# main_controller_board.net
KiCad netlist of a schematic drawn in EAGLE
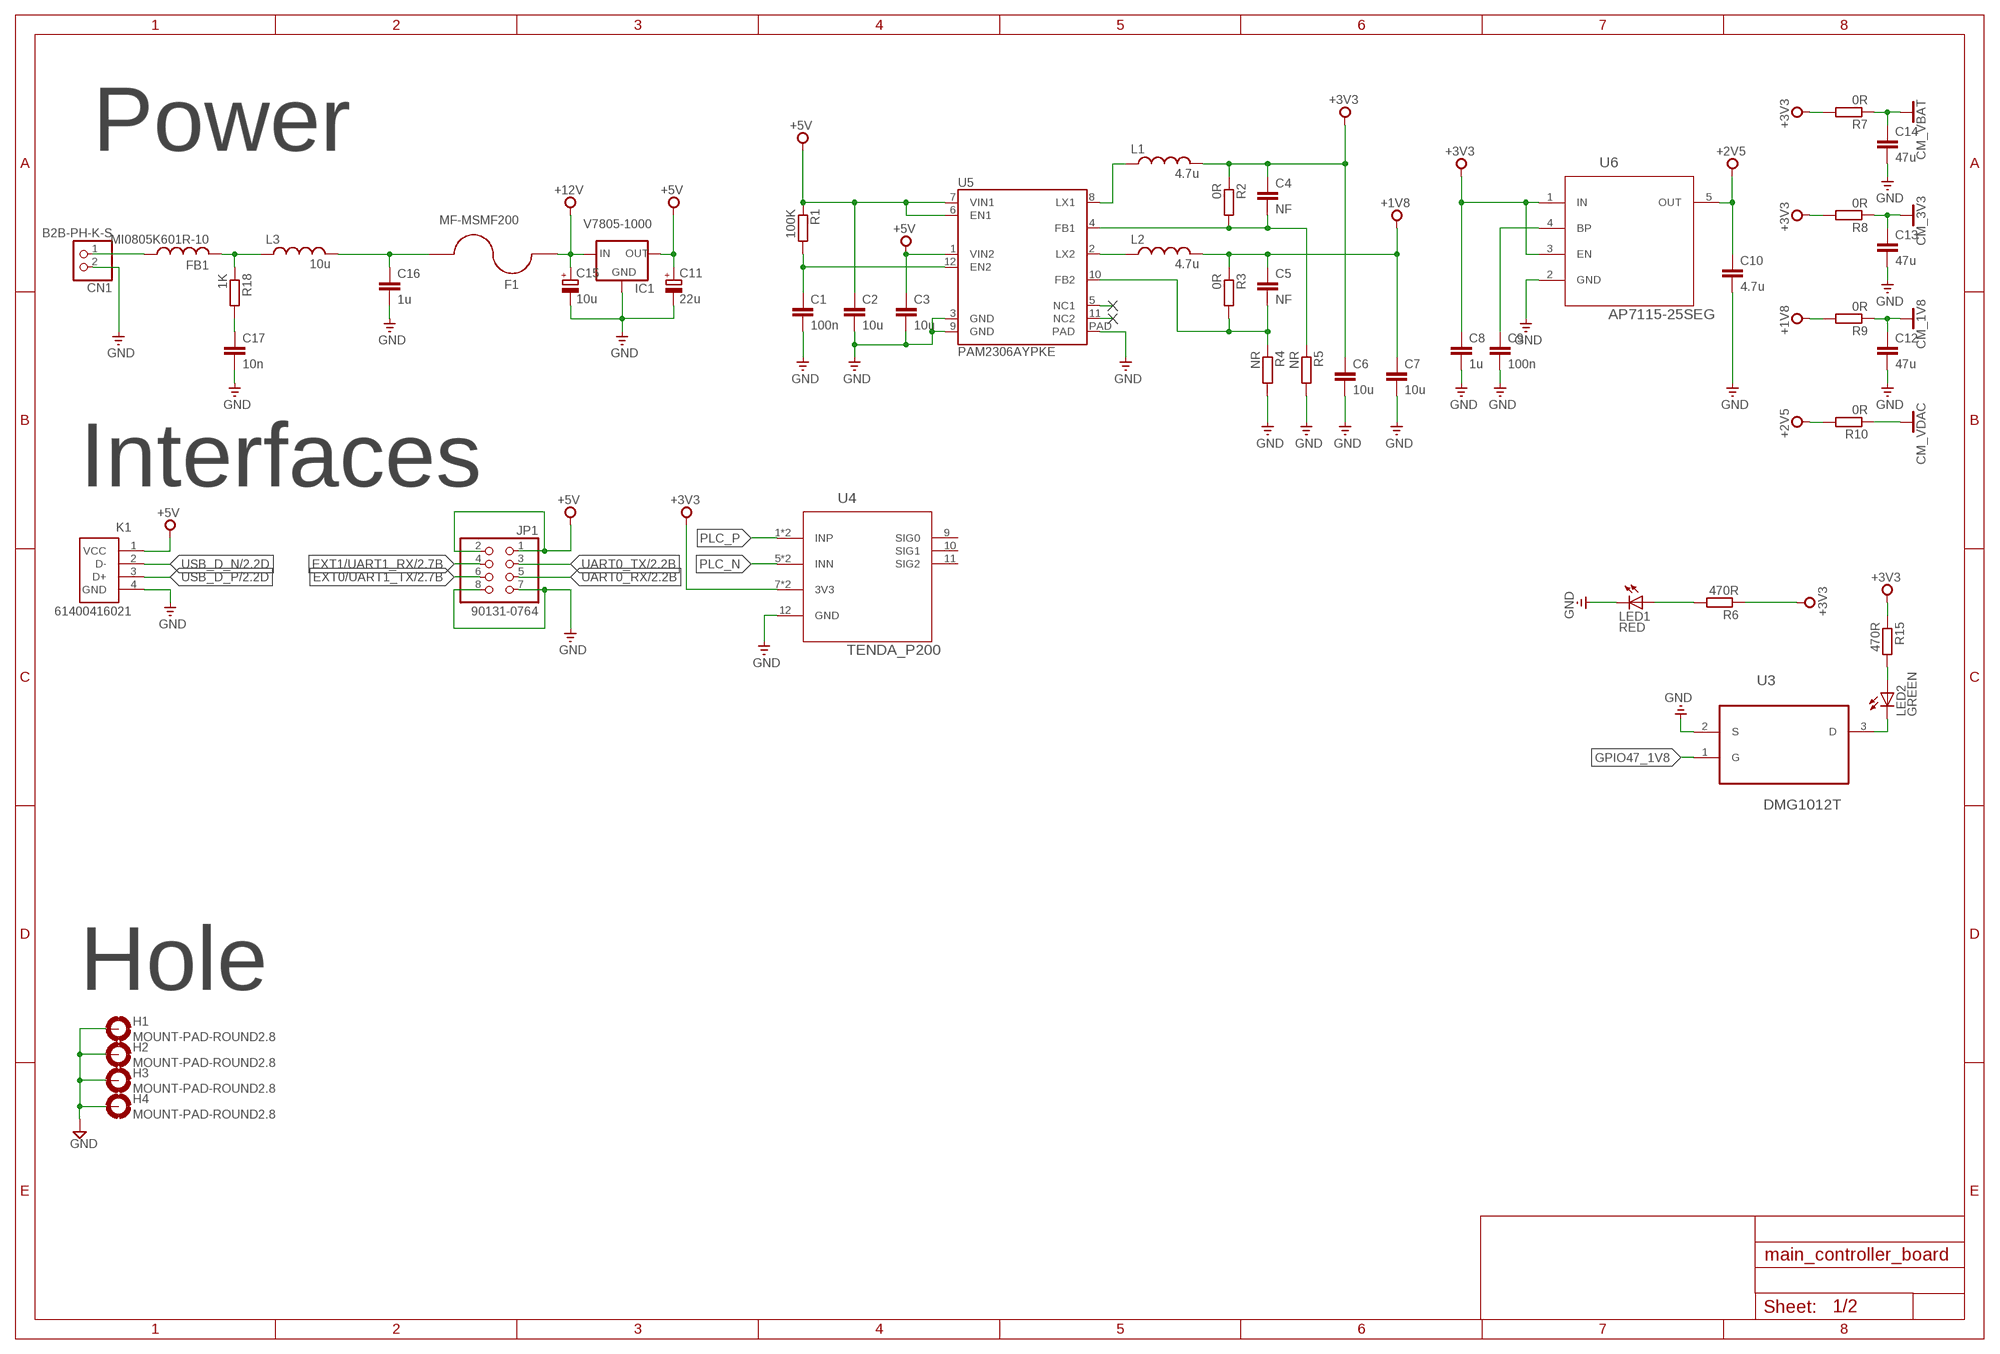
[diagram p0: schematic, sheet 1]
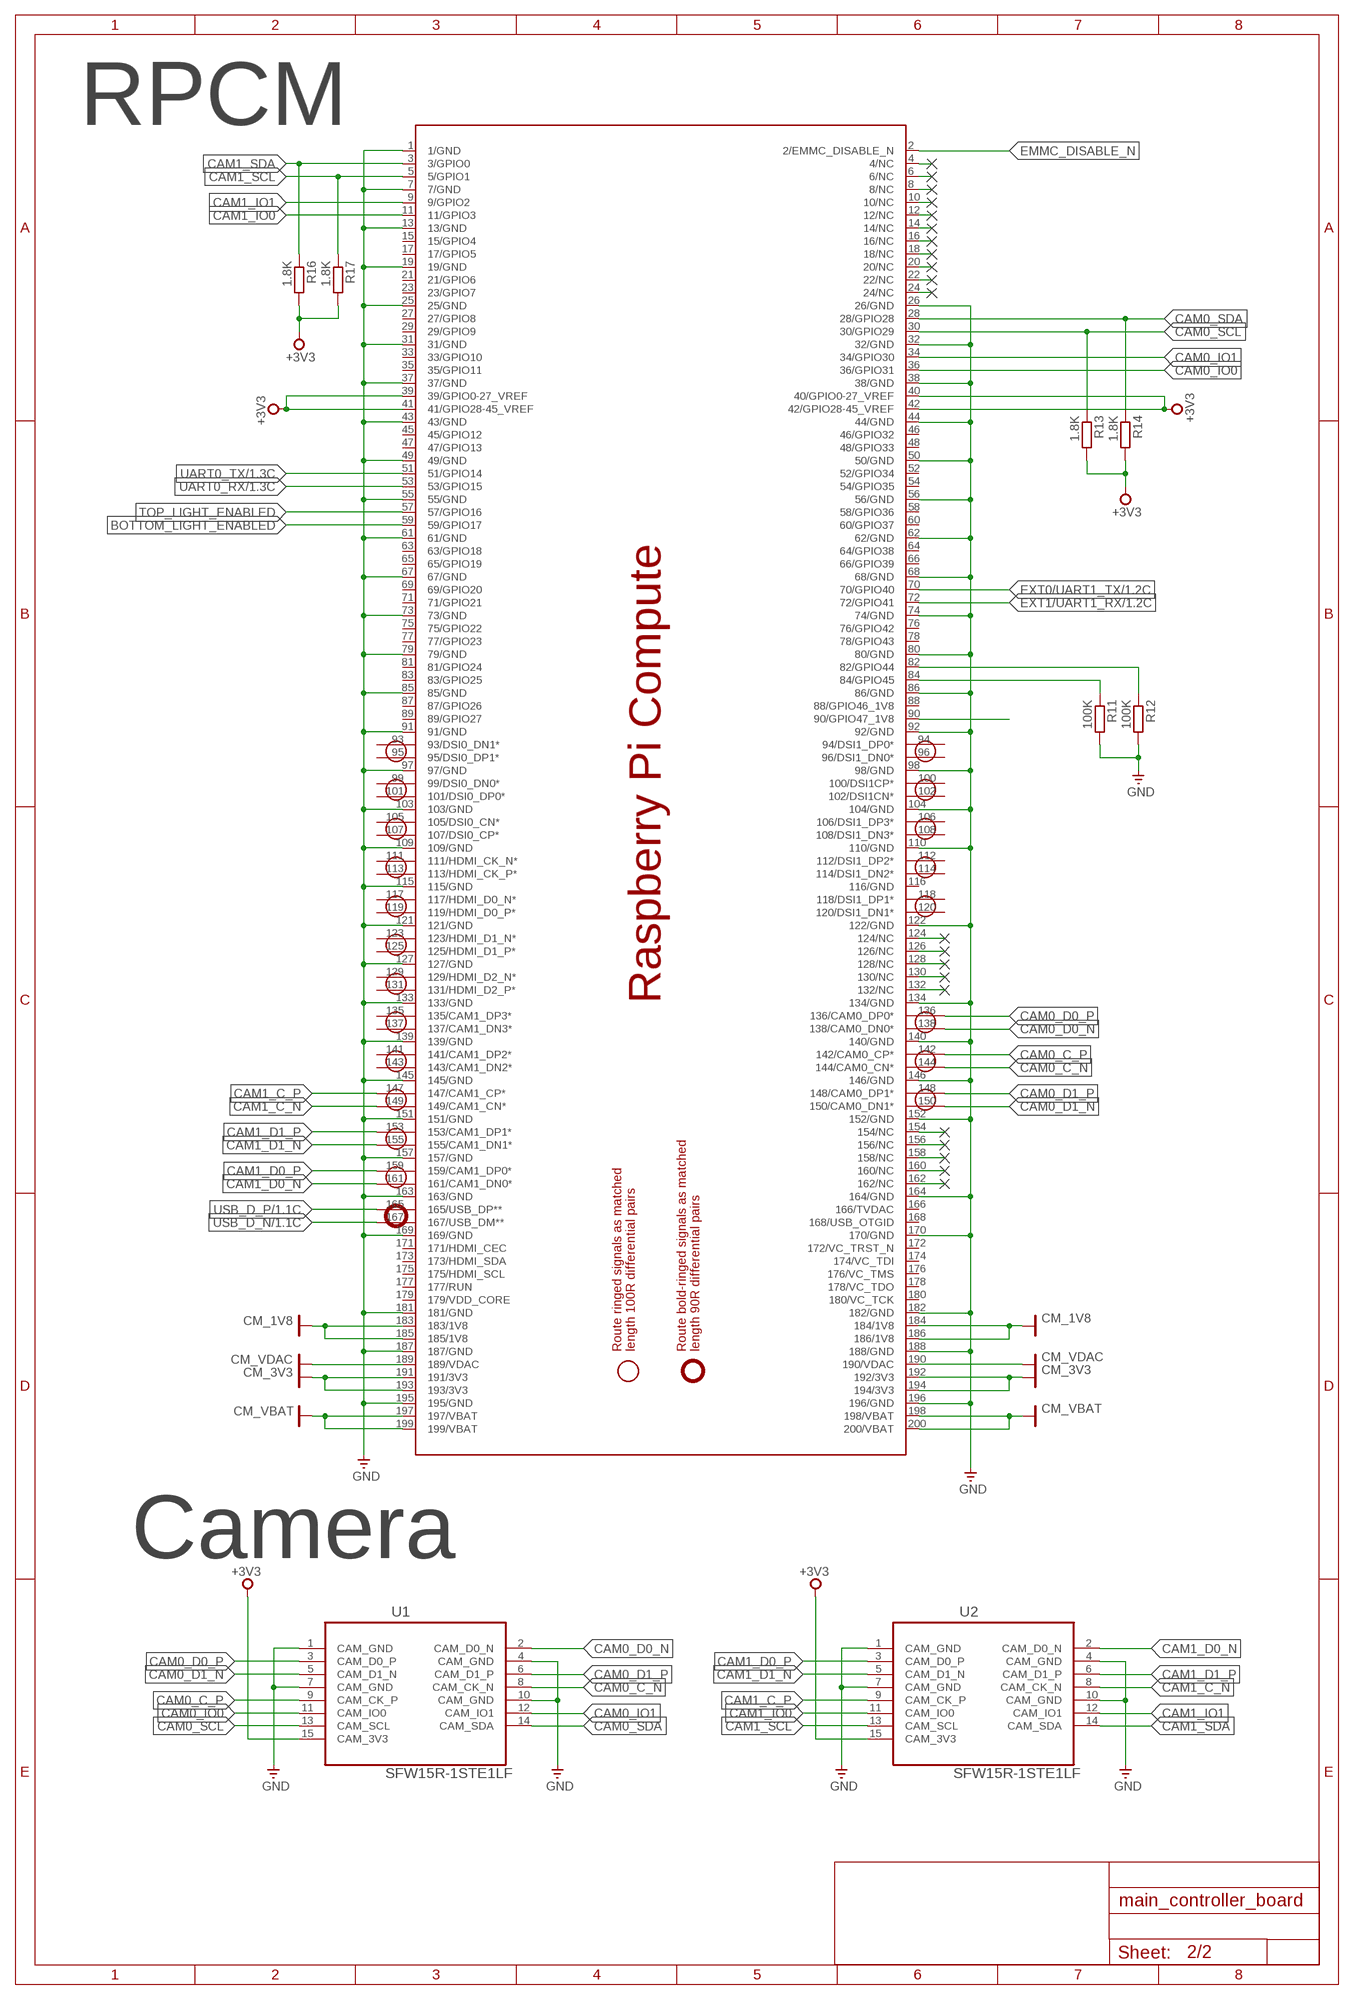
[diagram p1: schematic, sheet 2]

(export (version "E")
  (design (tool "Eeschema 10.0.6"))
  (components
    (comp (ref "PCB1")
      (value "1473005-4")
      (footprint "eagle-import:RPI_COMPUTE")
      (libsource (lib "eagle-import") (part "RPI_COMPUTE"))
    )
    (comp (ref "R11")
      (value "100K")
      (footprint "eagle-import:R0402")
      (libsource (lib "eagle-import") (part "R-EU_R0402"))
    )
    (comp (ref "R12")
      (value "100K")
      (footprint "eagle-import:R0402")
      (libsource (lib "eagle-import") (part "R-EU_R0402"))
    )
    (comp (ref "R13")
      (value "1.8K")
      (footprint "eagle-import:R0402")
      (libsource (lib "eagle-import") (part "R-EU_R0402"))
    )
    (comp (ref "R14")
      (value "1.8K")
      (footprint "eagle-import:R0402")
      (libsource (lib "eagle-import") (part "R-EU_R0402"))
    )
    (comp (ref "R16")
      (value "1.8K")
      (footprint "eagle-import:R0402")
      (libsource (lib "eagle-import") (part "R-EU_R0402"))
    )
    (comp (ref "R17")
      (value "1.8K")
      (footprint "eagle-import:R0402")
      (libsource (lib "eagle-import") (part "R-EU_R0402"))
    )
    (comp (ref "U1")
      (value "SFW15R-1STE1LF")
      (footprint "eagle-import:RPI_CAMERA")
      (fields (field (name "MPN") "SFW16R-1STE1LF"))
      (libsource (lib "eagle-import") (part "RPI_CAMERA"))
    )
    (comp (ref "U2")
      (value "SFW15R-1STE1LF")
      (footprint "eagle-import:RPI_CAMERA")
      (fields (field (name "MPN") "SFW16R-1STE1LF"))
      (libsource (lib "eagle-import") (part "RPI_CAMERA"))
    )
    (comp (ref "C1")
      (value "100n")
      (footprint "eagle-import:C0402")
      (libsource (lib "eagle-import") (part "C-EUC0402"))
    )
    (comp (ref "C2")
      (value "10u")
      (footprint "eagle-import:C0805")
      (libsource (lib "eagle-import") (part "C-EUC0805"))
    )
    (comp (ref "C3")
      (value "10u")
      (footprint "eagle-import:C0805")
      (libsource (lib "eagle-import") (part "C-EUC0805"))
    )
    (comp (ref "C4")
      (value "NF")
      (footprint "eagle-import:C0402")
      (libsource (lib "eagle-import") (part "C-EUC0402"))
    )
    (comp (ref "C5")
      (value "NF")
      (footprint "eagle-import:C0402")
      (libsource (lib "eagle-import") (part "C-EUC0402"))
    )
    (comp (ref "C6")
      (value "10u")
      (footprint "eagle-import:C0805")
      (libsource (lib "eagle-import") (part "C-EUC0805"))
    )
    (comp (ref "C7")
      (value "10u")
      (footprint "eagle-import:C0805")
      (libsource (lib "eagle-import") (part "C-EUC0805"))
    )
    (comp (ref "C8")
      (value "1u")
      (footprint "eagle-import:C0402")
      (libsource (lib "eagle-import") (part "C-EUC0402"))
    )
    (comp (ref "C9")
      (value "100n")
      (footprint "eagle-import:C0402")
      (libsource (lib "eagle-import") (part "C-EUC0402"))
    )
    (comp (ref "C10")
      (value "4.7u")
      (footprint "eagle-import:C0603")
      (libsource (lib "eagle-import") (part "C-EUC0603"))
    )
    (comp (ref "C11")
      (value "22u")
      (footprint "eagle-import:153CLV-0405")
      (libsource (lib "eagle-import") (part "CPOL-EU153CLV-0405"))
    )
    (comp (ref "C12")
      (value "47u")
      (footprint "eagle-import:C1206")
      (libsource (lib "eagle-import") (part "C-EUC1206"))
    )
    (comp (ref "C13")
      (value "47u")
      (footprint "eagle-import:C1206")
      (libsource (lib "eagle-import") (part "C-EUC1206"))
    )
    (comp (ref "C14")
      (value "47u")
      (footprint "eagle-import:C1206")
      (libsource (lib "eagle-import") (part "C-EUC1206"))
    )
    (comp (ref "C15")
      (value "10u")
      (footprint "eagle-import:153CLV-0405")
      (libsource (lib "eagle-import") (part "CPOL-EU153CLV-0405"))
    )
    (comp (ref "C16")
      (value "1u")
      (footprint "eagle-import:C0402")
      (libsource (lib "eagle-import") (part "C-EUC0402"))
    )
    (comp (ref "C17")
      (value "10n")
      (footprint "eagle-import:C0402")
      (libsource (lib "eagle-import") (part "C-EUC0402"))
    )
    (comp (ref "CN1")
      (value "B2B-PH-K-S")
      (footprint "eagle-import:JST-PH-2-THM")
      (libsource (lib "eagle-import") (part "JST_2PIN-THM"))
    )
    (comp (ref "F1")
      (value "MF-MSMF200")
      (footprint "eagle-import:1812")
      (fields (field (name "MANUFACTURER") "Bourns Inc.") (field (name "PART_NUMBER") "MF-MSMF075/24-2"))
      (libsource (lib "eagle-import") (part "MF-MSMF?075/24"))
    )
    (comp (ref "FB1")
      (value "MI0805K601R-10")
      (footprint "eagle-import:R0805")
      (libsource (lib "eagle-import") (part "FERRITESIZE_0805"))
    )
    (comp (ref "H1")
      (value "MOUNT-PAD-ROUND2.8")
      (footprint "eagle-import:2,8-PAD")
      (libsource (lib "eagle-import") (part "MOUNT-PAD-ROUND2.8"))
    )
    (comp (ref "H2")
      (value "MOUNT-PAD-ROUND2.8")
      (footprint "eagle-import:2,8-PAD")
      (libsource (lib "eagle-import") (part "MOUNT-PAD-ROUND2.8"))
    )
    (comp (ref "H3")
      (value "MOUNT-PAD-ROUND2.8")
      (footprint "eagle-import:2,8-PAD")
      (libsource (lib "eagle-import") (part "MOUNT-PAD-ROUND2.8"))
    )
    (comp (ref "H4")
      (value "MOUNT-PAD-ROUND2.8")
      (footprint "eagle-import:2,8-PAD")
      (libsource (lib "eagle-import") (part "MOUNT-PAD-ROUND2.8"))
    )
    (comp (ref "IC1")
      (value "V7805-1000")
      (footprint "eagle-import:DIP_3PIN")
      (libsource (lib "eagle-import") (part "VR_1OUTXX"))
    )
    (comp (ref "JP1")
      (value "90131-0764")
      (footprint "eagle-import:2X04")
      (libsource (lib "eagle-import") (part "PINHD-2X4"))
    )
    (comp (ref "K1")
      (value "61400416021")
      (footprint "eagle-import:61400416021")
      (libsource (lib "eagle-import") (part "61400416021"))
    )
    (comp (ref "L1")
      (value "4.7u")
      (footprint "eagle-import:BOURNS-SRN4018")
      (libsource (lib "eagle-import") (part "BOURNS-SRN4018"))
    )
    (comp (ref "L2")
      (value "4.7u")
      (footprint "eagle-import:BOURNS-SRN4018")
      (libsource (lib "eagle-import") (part "BOURNS-SRN4018"))
    )
    (comp (ref "L3")
      (value "10u")
      (footprint "eagle-import:BOURNS-SRN4018")
      (libsource (lib "eagle-import") (part "BOURNS-SRN4018"))
    )
    (comp (ref "LED1")
      (value "RED")
      (footprint "eagle-import:CHIP-LED0603")
      (libsource (lib "eagle-import") (part "LEDCHIP-LED0603"))
    )
    (comp (ref "LED2")
      (value "GREEN")
      (footprint "eagle-import:CHIP-LED0603")
      (libsource (lib "eagle-import") (part "LEDCHIP-LED0603"))
    )
    (comp (ref "R1")
      (value "100K")
      (footprint "eagle-import:R0402")
      (libsource (lib "eagle-import") (part "R-EU_R0402"))
    )
    (comp (ref "R2")
      (value "0R")
      (footprint "eagle-import:R0402")
      (libsource (lib "eagle-import") (part "R-EU_R0402"))
    )
    (comp (ref "R3")
      (value "0R")
      (footprint "eagle-import:R0402")
      (libsource (lib "eagle-import") (part "R-EU_R0402"))
    )
    (comp (ref "R4")
      (value "NR")
      (footprint "eagle-import:R0402")
      (libsource (lib "eagle-import") (part "R-EU_R0402"))
    )
    (comp (ref "R5")
      (value "NR")
      (footprint "eagle-import:R0402")
      (libsource (lib "eagle-import") (part "R-EU_R0402"))
    )
    (comp (ref "R6")
      (value "470R")
      (footprint "eagle-import:R0402")
      (libsource (lib "eagle-import") (part "R-EU_R0402"))
    )
    (comp (ref "R7")
      (value "0R")
      (footprint "eagle-import:R0805")
      (libsource (lib "eagle-import") (part "R-EU_R0805"))
    )
    (comp (ref "R8")
      (value "0R")
      (footprint "eagle-import:R0805")
      (libsource (lib "eagle-import") (part "R-EU_R0805"))
    )
    (comp (ref "R9")
      (value "0R")
      (footprint "eagle-import:R0805")
      (libsource (lib "eagle-import") (part "R-EU_R0805"))
    )
    (comp (ref "R10")
      (value "0R")
      (footprint "eagle-import:R0805")
      (libsource (lib "eagle-import") (part "R-EU_R0805"))
    )
    (comp (ref "R15")
      (value "470R")
      (footprint "eagle-import:R0402")
      (libsource (lib "eagle-import") (part "R-EU_R0402"))
    )
    (comp (ref "R18")
      (value "1K")
      (footprint "eagle-import:R0402")
      (libsource (lib "eagle-import") (part "R-EU_R0402"))
    )
    (comp (ref "U3")
      (value "DMG1012T")
      (footprint "eagle-import:SOT523")
      (libsource (lib "eagle-import") (part "DMG1012T"))
    )
    (comp (ref "U4")
      (value "TENDA_P200")
      (footprint "eagle-import:TENDA_P200")
      (libsource (lib "eagle-import") (part "TENDA_P200"))
    )
    (comp (ref "U5")
      (value "PAM2306AYPKE")
      (footprint "eagle-import:WDFN3X3-12L")
      (libsource (lib "eagle-import") (part "PAM2306"))
    )
    (comp (ref "U6")
      (value "AP7115-25SEG")
      (footprint "eagle-import:SOT353")
      (libsource (lib "eagle-import") (part "AP7115-XXSEG"))
    )
  )
  (nets
    (net (code "1") (name "+1V8") (class "Default")
      (node (ref "C5") (pin "1") (pinfunction "1_1") (pintype "passive"))
      (node (ref "C7") (pin "1") (pinfunction "1_1") (pintype "passive"))
      (node (ref "L2") (pin "P$1") (pinfunction "1_P$1") (pintype "passive"))
      (node (ref "R3") (pin "1") (pinfunction "1_1") (pintype "passive"))
      (node (ref "R9") (pin "2") (pinfunction "2_2") (pintype "passive"))
    )
    (net (code "2") (name "+2V5") (class "Default")
      (node (ref "C10") (pin "1") (pinfunction "1_1") (pintype "passive"))
      (node (ref "R10") (pin "2") (pinfunction "2_2") (pintype "passive"))
      (node (ref "U6") (pin "5") (pinfunction "OUT_5") (pintype "output"))
    )
    (net (code "3") (name "+3V3") (class "Default")
      (node (ref "C4") (pin "1") (pinfunction "1_1") (pintype "passive"))
      (node (ref "C6") (pin "1") (pinfunction "1_1") (pintype "passive"))
      (node (ref "C8") (pin "1") (pinfunction "1_1") (pintype "passive"))
      (node (ref "L1") (pin "P$1") (pinfunction "1_P$1") (pintype "passive"))
      (node (ref "PCB1") (pin "39") (pinfunction "39/GPIO0-27_VREF_39") (pintype "bidirectional"))
      (node (ref "PCB1") (pin "40") (pinfunction "40/GPIO0-27_VREF_40") (pintype "bidirectional"))
      (node (ref "PCB1") (pin "41") (pinfunction "41/GPIO28-45_VREF_41") (pintype "bidirectional"))
      (node (ref "PCB1") (pin "42") (pinfunction "42/GPIO28-45_VREF_42") (pintype "bidirectional"))
      (node (ref "R13") (pin "2") (pinfunction "2_2") (pintype "passive"))
      (node (ref "R14") (pin "2") (pinfunction "2_2") (pintype "passive"))
      (node (ref "R15") (pin "1") (pinfunction "1_1") (pintype "passive"))
      (node (ref "R16") (pin "2") (pinfunction "2_2") (pintype "passive"))
      (node (ref "R17") (pin "2") (pinfunction "2_2") (pintype "passive"))
      (node (ref "R2") (pin "1") (pinfunction "1_1") (pintype "passive"))
      (node (ref "R6") (pin "1") (pinfunction "1_1") (pintype "passive"))
      (node (ref "R7") (pin "2") (pinfunction "2_2") (pintype "passive"))
      (node (ref "R8") (pin "2") (pinfunction "2_2") (pintype "passive"))
      (node (ref "U1") (pin "15") (pinfunction "CAM_3V3_15") (pintype "passive"))
      (node (ref "U2") (pin "15") (pinfunction "CAM_3V3_15") (pintype "passive"))
      (node (ref "U4") (pin "7") (pinfunction "3V3_7") (pintype "passive"))
      (node (ref "U4") (pin "8") (pinfunction "3V3_8") (pintype "passive"))
      (node (ref "U6") (pin "1") (pinfunction "IN_1") (pintype "power_in"))
      (node (ref "U6") (pin "3") (pinfunction "EN_3") (pintype "passive"))
    )
    (net (code "4") (name "+5V") (class "Default")
      (node (ref "C11") (pin "+") (pinfunction "+_+") (pintype "passive"))
      (node (ref "C2") (pin "1") (pinfunction "1_1") (pintype "passive"))
      (node (ref "C3") (pin "1") (pinfunction "1_1") (pintype "passive"))
      (node (ref "IC1") (pin "OUT") (pinfunction "OUT_OUT") (pintype "passive"))
      (node (ref "JP1") (pin "1") (pinfunction "1_1") (pintype "passive"))
      (node (ref "JP1") (pin "2") (pinfunction "2_2") (pintype "passive"))
      (node (ref "K1") (pin "1") (pinfunction "VCC_1") (pintype "passive"))
      (node (ref "R1") (pin "1") (pinfunction "1_1") (pintype "passive"))
      (node (ref "U5") (pin "1") (pinfunction "VIN2_1") (pintype "bidirectional"))
      (node (ref "U5") (pin "6") (pinfunction "EN1_6") (pintype "bidirectional"))
      (node (ref "U5") (pin "7") (pinfunction "VIN1_7") (pintype "bidirectional"))
    )
    (net (code "5") (name "+12V") (class "Default")
      (node (ref "C15") (pin "+") (pinfunction "+_+") (pintype "passive"))
      (node (ref "F1") (pin "2") (pinfunction "2_2") (pintype "passive"))
      (node (ref "IC1") (pin "IN") (pinfunction "IN_IN") (pintype "input"))
    )
    (net (code "6") (name "BOTTOM_LIGHT_ENABLED") (class "Default")
      (node (ref "PCB1") (pin "59") (pinfunction "59/GPIO17_59") (pintype "bidirectional"))
    )
    (net (code "7") (name "CAM0_C_N") (class "Default")
      (node (ref "PCB1") (pin "144") (pinfunction "144/CAM0_CN*_144") (pintype "bidirectional"))
      (node (ref "U1") (pin "8") (pinfunction "CAM_CK_N_8") (pintype "passive"))
    )
    (net (code "8") (name "CAM0_C_P") (class "Default")
      (node (ref "PCB1") (pin "142") (pinfunction "142/CAM0_CP*_142") (pintype "bidirectional"))
      (node (ref "U1") (pin "9") (pinfunction "CAM_CK_P_9") (pintype "passive"))
    )
    (net (code "9") (name "CAM0_D0_N") (class "Default")
      (node (ref "PCB1") (pin "138") (pinfunction "138/CAM0_DN0*_138") (pintype "bidirectional"))
      (node (ref "U1") (pin "2") (pinfunction "CAM_D0_N_2") (pintype "passive"))
    )
    (net (code "10") (name "CAM0_D0_P") (class "Default")
      (node (ref "PCB1") (pin "136") (pinfunction "136/CAM0_DP0*_136") (pintype "bidirectional"))
      (node (ref "U1") (pin "3") (pinfunction "CAM_D0_P_3") (pintype "passive"))
    )
    (net (code "11") (name "CAM0_D1_N") (class "Default")
      (node (ref "PCB1") (pin "150") (pinfunction "150/CAM0_DN1*_150") (pintype "bidirectional"))
      (node (ref "U1") (pin "5") (pinfunction "CAM_D1_N_5") (pintype "passive"))
    )
    (net (code "12") (name "CAM0_D1_P") (class "Default")
      (node (ref "PCB1") (pin "148") (pinfunction "148/CAM0_DP1*_148") (pintype "bidirectional"))
      (node (ref "U1") (pin "6") (pinfunction "CAM_D1_P_6") (pintype "passive"))
    )
    (net (code "13") (name "CAM0_IO0") (class "Default")
      (node (ref "PCB1") (pin "36") (pinfunction "36/GPIO31_36") (pintype "bidirectional"))
      (node (ref "U1") (pin "11") (pinfunction "CAM_IO0_11") (pintype "passive"))
    )
    (net (code "14") (name "CAM0_IO1") (class "Default")
      (node (ref "PCB1") (pin "34") (pinfunction "34/GPIO30_34") (pintype "bidirectional"))
      (node (ref "U1") (pin "12") (pinfunction "CAM_IO1_12") (pintype "passive"))
    )
    (net (code "15") (name "CAM0_SCL") (class "Default")
      (node (ref "PCB1") (pin "30") (pinfunction "30/GPIO29_30") (pintype "bidirectional"))
      (node (ref "R13") (pin "1") (pinfunction "1_1") (pintype "passive"))
      (node (ref "U1") (pin "13") (pinfunction "CAM_SCL_13") (pintype "passive"))
    )
    (net (code "16") (name "CAM0_SDA") (class "Default")
      (node (ref "PCB1") (pin "28") (pinfunction "28/GPIO28_28") (pintype "bidirectional"))
      (node (ref "R14") (pin "1") (pinfunction "1_1") (pintype "passive"))
      (node (ref "U1") (pin "14") (pinfunction "CAM_SDA_14") (pintype "passive"))
    )
    (net (code "17") (name "CAM1_C_N") (class "Default")
      (node (ref "PCB1") (pin "149") (pinfunction "149/CAM1_CN*_149") (pintype "bidirectional"))
      (node (ref "U2") (pin "8") (pinfunction "CAM_CK_N_8") (pintype "passive"))
    )
    (net (code "18") (name "CAM1_C_P") (class "Default")
      (node (ref "PCB1") (pin "147") (pinfunction "147/CAM1_CP*_147") (pintype "bidirectional"))
      (node (ref "U2") (pin "9") (pinfunction "CAM_CK_P_9") (pintype "passive"))
    )
    (net (code "19") (name "CAM1_D0_N") (class "Default")
      (node (ref "PCB1") (pin "161") (pinfunction "161/CAM1_DN0*_161") (pintype "bidirectional"))
      (node (ref "U2") (pin "2") (pinfunction "CAM_D0_N_2") (pintype "passive"))
    )
    (net (code "20") (name "CAM1_D0_P") (class "Default")
      (node (ref "PCB1") (pin "159") (pinfunction "159/CAM1_DP0*_159") (pintype "bidirectional"))
      (node (ref "U2") (pin "3") (pinfunction "CAM_D0_P_3") (pintype "passive"))
    )
    (net (code "21") (name "CAM1_D1_N") (class "Default")
      (node (ref "PCB1") (pin "155") (pinfunction "155/CAM1_DN1*_155") (pintype "bidirectional"))
      (node (ref "U2") (pin "5") (pinfunction "CAM_D1_N_5") (pintype "passive"))
    )
    (net (code "22") (name "CAM1_D1_P") (class "Default")
      (node (ref "PCB1") (pin "153") (pinfunction "153/CAM1_DP1*_153") (pintype "bidirectional"))
      (node (ref "U2") (pin "6") (pinfunction "CAM_D1_P_6") (pintype "passive"))
    )
    (net (code "23") (name "CAM1_IO0") (class "Default")
      (node (ref "PCB1") (pin "11") (pinfunction "11/GPIO3_11") (pintype "bidirectional"))
      (node (ref "U2") (pin "11") (pinfunction "CAM_IO0_11") (pintype "passive"))
    )
    (net (code "24") (name "CAM1_IO1") (class "Default")
      (node (ref "PCB1") (pin "9") (pinfunction "9/GPIO2_9") (pintype "bidirectional"))
      (node (ref "U2") (pin "12") (pinfunction "CAM_IO1_12") (pintype "passive"))
    )
    (net (code "25") (name "CAM1_SCL") (class "Default")
      (node (ref "PCB1") (pin "5") (pinfunction "5/GPIO1_5") (pintype "bidirectional"))
      (node (ref "R17") (pin "1") (pinfunction "1_1") (pintype "passive"))
      (node (ref "U2") (pin "13") (pinfunction "CAM_SCL_13") (pintype "passive"))
    )
    (net (code "26") (name "CAM1_SDA") (class "Default")
      (node (ref "PCB1") (pin "3") (pinfunction "3/GPIO0_3") (pintype "bidirectional"))
      (node (ref "R16") (pin "1") (pinfunction "1_1") (pintype "passive"))
      (node (ref "U2") (pin "14") (pinfunction "CAM_SDA_14") (pintype "passive"))
    )
    (net (code "27") (name "CM_1V8") (class "Default")
      (node (ref "C12") (pin "1") (pinfunction "1_1") (pintype "passive"))
      (node (ref "PCB1") (pin "183") (pinfunction "183/1V8_183") (pintype "bidirectional"))
      (node (ref "PCB1") (pin "184") (pinfunction "184/1V8_184") (pintype "bidirectional"))
      (node (ref "PCB1") (pin "185") (pinfunction "185/1V8_185") (pintype "bidirectional"))
      (node (ref "PCB1") (pin "186") (pinfunction "186/1V8_186") (pintype "bidirectional"))
      (node (ref "R9") (pin "1") (pinfunction "1_1") (pintype "passive"))
    )
    (net (code "28") (name "CM_3V3") (class "Default")
      (node (ref "C13") (pin "1") (pinfunction "1_1") (pintype "passive"))
      (node (ref "PCB1") (pin "191") (pinfunction "191/3V3_191") (pintype "bidirectional"))
      (node (ref "PCB1") (pin "192") (pinfunction "192/3V3_192") (pintype "bidirectional"))
      (node (ref "PCB1") (pin "193") (pinfunction "193/3V3_193") (pintype "bidirectional"))
      (node (ref "PCB1") (pin "194") (pinfunction "194/3V3_194") (pintype "bidirectional"))
      (node (ref "R8") (pin "1") (pinfunction "1_1") (pintype "passive"))
    )
    (net (code "29") (name "CM_VBAT") (class "Default")
      (node (ref "C14") (pin "1") (pinfunction "1_1") (pintype "passive"))
      (node (ref "PCB1") (pin "197") (pinfunction "197/VBAT_197") (pintype "bidirectional"))
      (node (ref "PCB1") (pin "198") (pinfunction "198/VBAT_198") (pintype "bidirectional"))
      (node (ref "PCB1") (pin "199") (pinfunction "199/VBAT_199") (pintype "bidirectional"))
      (node (ref "PCB1") (pin "200") (pinfunction "200/VBAT_200") (pintype "bidirectional"))
      (node (ref "R7") (pin "1") (pinfunction "1_1") (pintype "passive"))
    )
    (net (code "30") (name "CM_VDAC") (class "Default")
      (node (ref "PCB1") (pin "189") (pinfunction "189/VDAC_189") (pintype "bidirectional"))
      (node (ref "PCB1") (pin "190") (pinfunction "190/VDAC_190") (pintype "bidirectional"))
      (node (ref "R10") (pin "1") (pinfunction "1_1") (pintype "passive"))
    )
    (net (code "31") (name "EMMC_DISABLE_N") (class "Default")
      (node (ref "PCB1") (pin "2") (pinfunction "2/EMMC_DISABLE_N_2") (pintype "bidirectional"))
    )
    (net (code "32") (name "EXT0{slash}UART1_TX") (class "Default")
      (node (ref "JP1") (pin "6") (pinfunction "6_6") (pintype "passive"))
      (node (ref "PCB1") (pin "70") (pinfunction "70/GPIO40_70") (pintype "bidirectional"))
    )
    (net (code "33") (name "EXT1{slash}UART1_RX") (class "Default")
      (node (ref "JP1") (pin "4") (pinfunction "4_4") (pintype "passive"))
      (node (ref "PCB1") (pin "72") (pinfunction "72/GPIO41_72") (pintype "bidirectional"))
    )
    (net (code "34") (name "GND") (class "Default")
      (node (ref "C1") (pin "2") (pinfunction "2_2") (pintype "passive"))
      (node (ref "C10") (pin "2") (pinfunction "2_2") (pintype "passive"))
      (node (ref "C11") (pin "-") (pinfunction "-_-") (pintype "passive"))
      (node (ref "C12") (pin "2") (pinfunction "2_2") (pintype "passive"))
      (node (ref "C13") (pin "2") (pinfunction "2_2") (pintype "passive"))
      (node (ref "C14") (pin "2") (pinfunction "2_2") (pintype "passive"))
      (node (ref "C15") (pin "-") (pinfunction "-_-") (pintype "passive"))
      (node (ref "C16") (pin "2") (pinfunction "2_2") (pintype "passive"))
      (node (ref "C17") (pin "2") (pinfunction "2_2") (pintype "passive"))
      (node (ref "C2") (pin "2") (pinfunction "2_2") (pintype "passive"))
      (node (ref "C3") (pin "2") (pinfunction "2_2") (pintype "passive"))
      (node (ref "C6") (pin "2") (pinfunction "2_2") (pintype "passive"))
      (node (ref "C7") (pin "2") (pinfunction "2_2") (pintype "passive"))
      (node (ref "C8") (pin "2") (pinfunction "2_2") (pintype "passive"))
      (node (ref "C9") (pin "2") (pinfunction "2_2") (pintype "passive"))
      (node (ref "CN1") (pin "2") (pinfunction "1_2") (pintype "passive"))
      (node (ref "H1") (pin "B2,8") (pinfunction "MOUNT_B2,8") (pintype "passive"))
      (node (ref "H2") (pin "B2,8") (pinfunction "MOUNT_B2,8") (pintype "passive"))
      (node (ref "H3") (pin "B2,8") (pinfunction "MOUNT_B2,8") (pintype "passive"))
      (node (ref "H4") (pin "B2,8") (pinfunction "MOUNT_B2,8") (pintype "passive"))
      (node (ref "IC1") (pin "GND") (pinfunction "GND_GND") (pintype "input"))
      (node (ref "JP1") (pin "7") (pinfunction "7_7") (pintype "passive"))
      (node (ref "JP1") (pin "8") (pinfunction "8_8") (pintype "passive"))
      (node (ref "K1") (pin "4") (pinfunction "GND_4") (pintype "passive"))
      (node (ref "LED1") (pin "C") (pinfunction "C_C") (pintype "passive"))
      (node (ref "PCB1") (pin "1") (pinfunction "1/GND_1") (pintype "bidirectional"))
      (node (ref "PCB1") (pin "103") (pinfunction "103/GND_103") (pintype "bidirectional"))
      (node (ref "PCB1") (pin "104") (pinfunction "104/GND_104") (pintype "bidirectional"))
      (node (ref "PCB1") (pin "109") (pinfunction "109/GND_109") (pintype "bidirectional"))
      (node (ref "PCB1") (pin "110") (pinfunction "110/GND_110") (pintype "bidirectional"))
      (node (ref "PCB1") (pin "115") (pinfunction "115/GND_115") (pintype "bidirectional"))
      (node (ref "PCB1") (pin "121") (pinfunction "121/GND_121") (pintype "bidirectional"))
      (node (ref "PCB1") (pin "122") (pinfunction "122/GND_122") (pintype "bidirectional"))
      (node (ref "PCB1") (pin "127") (pinfunction "127/GND_127") (pintype "bidirectional"))
      (node (ref "PCB1") (pin "13") (pinfunction "13/GND_13") (pintype "bidirectional"))
      (node (ref "PCB1") (pin "133") (pinfunction "133/GND_133") (pintype "bidirectional"))
      (node (ref "PCB1") (pin "134") (pinfunction "134/GND_134") (pintype "bidirectional"))
      (node (ref "PCB1") (pin "139") (pinfunction "139/GND_139") (pintype "bidirectional"))
      (node (ref "PCB1") (pin "140") (pinfunction "140/GND_140") (pintype "bidirectional"))
      (node (ref "PCB1") (pin "145") (pinfunction "145/GND_145") (pintype "bidirectional"))
      (node (ref "PCB1") (pin "146") (pinfunction "146/GND_146") (pintype "bidirectional"))
      (node (ref "PCB1") (pin "151") (pinfunction "151/GND_151") (pintype "bidirectional"))
      (node (ref "PCB1") (pin "152") (pinfunction "152/GND_152") (pintype "bidirectional"))
      (node (ref "PCB1") (pin "157") (pinfunction "157/GND_157") (pintype "bidirectional"))
      (node (ref "PCB1") (pin "163") (pinfunction "163/GND_163") (pintype "bidirectional"))
      (node (ref "PCB1") (pin "164") (pinfunction "164/GND_164") (pintype "bidirectional"))
      (node (ref "PCB1") (pin "169") (pinfunction "169/GND_169") (pintype "bidirectional"))
      (node (ref "PCB1") (pin "170") (pinfunction "170/GND_170") (pintype "bidirectional"))
      (node (ref "PCB1") (pin "181") (pinfunction "181/GND_181") (pintype "bidirectional"))
      (node (ref "PCB1") (pin "182") (pinfunction "182/GND_182") (pintype "bidirectional"))
      (node (ref "PCB1") (pin "187") (pinfunction "187/GND_187") (pintype "bidirectional"))
      (node (ref "PCB1") (pin "188") (pinfunction "188/GND_188") (pintype "bidirectional"))
      (node (ref "PCB1") (pin "19") (pinfunction "19/GND_19") (pintype "bidirectional"))
      (node (ref "PCB1") (pin "195") (pinfunction "195/GND_195") (pintype "bidirectional"))
      (node (ref "PCB1") (pin "196") (pinfunction "196/GND_196") (pintype "bidirectional"))
      (node (ref "PCB1") (pin "25") (pinfunction "25/GND_25") (pintype "bidirectional"))
      (node (ref "PCB1") (pin "26") (pinfunction "26/GND_26") (pintype "bidirectional"))
      (node (ref "PCB1") (pin "31") (pinfunction "31/GND_31") (pintype "bidirectional"))
      (node (ref "PCB1") (pin "32") (pinfunction "32/GND_32") (pintype "bidirectional"))
      (node (ref "PCB1") (pin "37") (pinfunction "37/GND_37") (pintype "bidirectional"))
      (node (ref "PCB1") (pin "38") (pinfunction "38/GND_38") (pintype "bidirectional"))
      (node (ref "PCB1") (pin "43") (pinfunction "43/GND_43") (pintype "bidirectional"))
      (node (ref "PCB1") (pin "44") (pinfunction "44/GND_44") (pintype "bidirectional"))
      (node (ref "PCB1") (pin "49") (pinfunction "49/GND_49") (pintype "bidirectional"))
      (node (ref "PCB1") (pin "50") (pinfunction "50/GND_50") (pintype "bidirectional"))
      (node (ref "PCB1") (pin "55") (pinfunction "55/GND_55") (pintype "bidirectional"))
      (node (ref "PCB1") (pin "56") (pinfunction "56/GND_56") (pintype "bidirectional"))
      (node (ref "PCB1") (pin "61") (pinfunction "61/GND_61") (pintype "bidirectional"))
      (node (ref "PCB1") (pin "62") (pinfunction "62/GND_62") (pintype "bidirectional"))
      (node (ref "PCB1") (pin "67") (pinfunction "67/GND_67") (pintype "bidirectional"))
      (node (ref "PCB1") (pin "68") (pinfunction "68/GND_68") (pintype "bidirectional"))
      (node (ref "PCB1") (pin "7") (pinfunction "7/GND_7") (pintype "bidirectional"))
      (node (ref "PCB1") (pin "73") (pinfunction "73/GND_73") (pintype "bidirectional"))
      (node (ref "PCB1") (pin "74") (pinfunction "74/GND_74") (pintype "bidirectional"))
      (node (ref "PCB1") (pin "79") (pinfunction "79/GND_79") (pintype "bidirectional"))
      (node (ref "PCB1") (pin "80") (pinfunction "80/GND_80") (pintype "bidirectional"))
      (node (ref "PCB1") (pin "85") (pinfunction "85/GND_85") (pintype "bidirectional"))
      (node (ref "PCB1") (pin "86") (pinfunction "86/GND_86") (pintype "bidirectional"))
      (node (ref "PCB1") (pin "91") (pinfunction "91/GND_91") (pintype "bidirectional"))
      (node (ref "PCB1") (pin "92") (pinfunction "92/GND_92") (pintype "bidirectional"))
      (node (ref "PCB1") (pin "97") (pinfunction "97/GND_97") (pintype "bidirectional"))
      (node (ref "PCB1") (pin "98") (pinfunction "98/GND_98") (pintype "bidirectional"))
      (node (ref "R11") (pin "2") (pinfunction "2_2") (pintype "passive"))
      (node (ref "R12") (pin "2") (pinfunction "2_2") (pintype "passive"))
      (node (ref "R4") (pin "2") (pinfunction "2_2") (pintype "passive"))
      (node (ref "R5") (pin "2") (pinfunction "2_2") (pintype "passive"))
      (node (ref "U1") (pin "1") (pinfunction "CAM_GND_1") (pintype "passive"))
      (node (ref "U1") (pin "10") (pinfunction "CAM_GND_10") (pintype "passive"))
      (node (ref "U1") (pin "4") (pinfunction "CAM_GND_4") (pintype "passive"))
      (node (ref "U1") (pin "7") (pinfunction "CAM_GND_7") (pintype "passive"))
      (node (ref "U2") (pin "1") (pinfunction "CAM_GND_1") (pintype "passive"))
      (node (ref "U2") (pin "10") (pinfunction "CAM_GND_10") (pintype "passive"))
      (node (ref "U2") (pin "4") (pinfunction "CAM_GND_4") (pintype "passive"))
      (node (ref "U2") (pin "7") (pinfunction "CAM_GND_7") (pintype "passive"))
      (node (ref "U3") (pin "2") (pinfunction "S_2") (pintype "passive"))
      (node (ref "U4") (pin "12") (pinfunction "GND_12") (pintype "passive"))
      (node (ref "U5") (pin "3") (pinfunction "GND_3") (pintype "bidirectional"))
      (node (ref "U5") (pin "9") (pinfunction "GND_9") (pintype "bidirectional"))
      (node (ref "U5") (pin "PAD") (pinfunction "PAD_PAD") (pintype "bidirectional"))
      (node (ref "U6") (pin "2") (pinfunction "GND_2") (pintype "passive"))
    )
    (net (code "35") (name "GPIO47_1V8") (class "Default")
      (node (ref "PCB1") (pin "90") (pinfunction "90/GPIO47_1V8_90") (pintype "bidirectional"))
      (node (ref "U3") (pin "1") (pinfunction "G_1") (pintype "power_in"))
    )
    (net (code "36") (name "Net-(C17-Pad1)") (class "Default")
      (node (ref "C17") (pin "1") (pinfunction "1_1") (pintype "passive"))
      (node (ref "R18") (pin "2") (pinfunction "2_2") (pintype "passive"))
    )
    (net (code "37") (name "Net-(CN1-2)") (class "Default")
      (node (ref "CN1") (pin "1") (pinfunction "2_1") (pintype "passive"))
      (node (ref "FB1") (pin "1") (pinfunction "1_1") (pintype "passive"))
    )
    (net (code "38") (name "Net-(L1-2)") (class "Default")
      (node (ref "L1") (pin "P$2") (pinfunction "2_P$2") (pintype "passive"))
      (node (ref "U5") (pin "8") (pinfunction "LX1_8") (pintype "bidirectional"))
    )
    (net (code "39") (name "Net-(L2-2)") (class "Default")
      (node (ref "L2") (pin "P$2") (pinfunction "2_P$2") (pintype "passive"))
      (node (ref "U5") (pin "2") (pinfunction "LX2_2") (pintype "bidirectional"))
    )
    (net (code "40") (name "Net-(L3-1)") (class "Default")
      (node (ref "C16") (pin "1") (pinfunction "1_1") (pintype "passive"))
      (node (ref "F1") (pin "1") (pinfunction "1_1") (pintype "passive"))
      (node (ref "L3") (pin "P$1") (pinfunction "1_P$1") (pintype "passive"))
    )
    (net (code "41") (name "Net-(L3-2)") (class "Default")
      (node (ref "FB1") (pin "2") (pinfunction "2_2") (pintype "passive"))
      (node (ref "L3") (pin "P$2") (pinfunction "2_P$2") (pintype "passive"))
      (node (ref "R18") (pin "1") (pinfunction "1_1") (pintype "passive"))
    )
    (net (code "42") (name "Net-(LED1-PadA)") (class "Default")
      (node (ref "LED1") (pin "A") (pinfunction "A_A") (pintype "passive"))
      (node (ref "R6") (pin "2") (pinfunction "2_2") (pintype "passive"))
    )
    (net (code "43") (name "Net-(LED2-PadA)") (class "Default")
      (node (ref "LED2") (pin "A") (pinfunction "A_A") (pintype "passive"))
      (node (ref "R15") (pin "2") (pinfunction "2_2") (pintype "passive"))
    )
    (net (code "44") (name "Net-(PCB1-82{slash}GPIO44)") (class "Default")
      (node (ref "PCB1") (pin "82") (pinfunction "82/GPIO44_82") (pintype "bidirectional"))
      (node (ref "R12") (pin "1") (pinfunction "1_1") (pintype "passive"))
    )
    (net (code "45") (name "Net-(PCB1-84{slash}GPIO45)") (class "Default")
      (node (ref "PCB1") (pin "84") (pinfunction "84/GPIO45_84") (pintype "bidirectional"))
      (node (ref "R11") (pin "1") (pinfunction "1_1") (pintype "passive"))
    )
    (net (code "46") (name "Net-(U3-D)") (class "Default")
      (node (ref "LED2") (pin "C") (pinfunction "C_C") (pintype "passive"))
      (node (ref "U3") (pin "3") (pinfunction "D_3") (pintype "output"))
    )
    (net (code "47") (name "Net-(U5-EN2)") (class "Default")
      (node (ref "C1") (pin "1") (pinfunction "1_1") (pintype "passive"))
      (node (ref "R1") (pin "2") (pinfunction "2_2") (pintype "passive"))
      (node (ref "U5") (pin "12") (pinfunction "EN2_12") (pintype "bidirectional"))
    )
    (net (code "48") (name "Net-(U5-FB1)") (class "Default")
      (node (ref "C4") (pin "2") (pinfunction "2_2") (pintype "passive"))
      (node (ref "R2") (pin "2") (pinfunction "2_2") (pintype "passive"))
      (node (ref "R5") (pin "1") (pinfunction "1_1") (pintype "passive"))
      (node (ref "U5") (pin "4") (pinfunction "FB1_4") (pintype "bidirectional"))
    )
    (net (code "49") (name "Net-(U5-FB2)") (class "Default")
      (node (ref "C5") (pin "2") (pinfunction "2_2") (pintype "passive"))
      (node (ref "R3") (pin "2") (pinfunction "2_2") (pintype "passive"))
      (node (ref "R4") (pin "1") (pinfunction "1_1") (pintype "passive"))
      (node (ref "U5") (pin "10") (pinfunction "FB2_10") (pintype "bidirectional"))
    )
    (net (code "50") (name "Net-(U6-BP)") (class "Default")
      (node (ref "C9") (pin "1") (pinfunction "1_1") (pintype "passive"))
      (node (ref "U6") (pin "4") (pinfunction "BP_4") (pintype "input"))
    )
    (net (code "51") (name "PLC_N") (class "Default")
      (node (ref "U4") (pin "5") (pinfunction "INN_5") (pintype "input"))
      (node (ref "U4") (pin "6") (pinfunction "INN_6") (pintype "input"))
    )
    (net (code "52") (name "PLC_P") (class "Default")
      (node (ref "U4") (pin "1") (pinfunction "INP_1") (pintype "input"))
      (node (ref "U4") (pin "2") (pinfunction "INP_2") (pintype "input"))
    )
    (net (code "53") (name "TOP_LIGHT_ENABLED") (class "Default")
      (node (ref "PCB1") (pin "57") (pinfunction "57/GPIO16_57") (pintype "bidirectional"))
    )
    (net (code "54") (name "UART0_RX") (class "Default")
      (node (ref "JP1") (pin "5") (pinfunction "5_5") (pintype "passive"))
      (node (ref "PCB1") (pin "53") (pinfunction "53/GPIO15_53") (pintype "bidirectional"))
    )
    (net (code "55") (name "UART0_TX") (class "Default")
      (node (ref "JP1") (pin "3") (pinfunction "3_3") (pintype "passive"))
      (node (ref "PCB1") (pin "51") (pinfunction "51/GPIO14_51") (pintype "bidirectional"))
    )
    (net (code "56") (name "USB_D_N") (class "Default")
      (node (ref "K1") (pin "2") (pinfunction "D-_2") (pintype "passive"))
      (node (ref "PCB1") (pin "167") (pinfunction "167/USB_DM**_167") (pintype "bidirectional"))
    )
    (net (code "57") (name "USB_D_P") (class "Default")
      (node (ref "K1") (pin "3") (pinfunction "D+_3") (pintype "passive"))
      (node (ref "PCB1") (pin "165") (pinfunction "165/USB_DP**_165") (pintype "bidirectional"))
    )
    (net (code "58") (name "unconnected-(PCB1-4{slash}NC-Pad4)") (class "Default")
      (node (ref "PCB1") (pin "4") (pinfunction "4/NC_4") (pintype "bidirectional"))
    )
    (net (code "59") (name "unconnected-(PCB1-6{slash}NC-Pad6)") (class "Default")
      (node (ref "PCB1") (pin "6") (pinfunction "6/NC_6") (pintype "bidirectional"))
    )
    (net (code "60") (name "unconnected-(PCB1-8{slash}NC-Pad8)") (class "Default")
      (node (ref "PCB1") (pin "8") (pinfunction "8/NC_8") (pintype "bidirectional"))
    )
    (net (code "61") (name "unconnected-(PCB1-10{slash}NC-Pad10)") (class "Default")
      (node (ref "PCB1") (pin "10") (pinfunction "10/NC_10") (pintype "bidirectional"))
    )
    (net (code "62") (name "unconnected-(PCB1-12{slash}NC-Pad12)") (class "Default")
      (node (ref "PCB1") (pin "12") (pinfunction "12/NC_12") (pintype "bidirectional"))
    )
    (net (code "63") (name "unconnected-(PCB1-14{slash}NC-Pad14)") (class "Default")
      (node (ref "PCB1") (pin "14") (pinfunction "14/NC_14") (pintype "bidirectional"))
    )
    (net (code "64") (name "unconnected-(PCB1-15{slash}GPIO4-Pad15)") (class "Default")
      (node (ref "PCB1") (pin "15") (pinfunction "15/GPIO4_15") (pintype "bidirectional"))
    )
    (net (code "65") (name "unconnected-(PCB1-16{slash}NC-Pad16)") (class "Default")
      (node (ref "PCB1") (pin "16") (pinfunction "16/NC_16") (pintype "bidirectional"))
    )
    (net (code "66") (name "unconnected-(PCB1-17{slash}GPIO5-Pad17)") (class "Default")
      (node (ref "PCB1") (pin "17") (pinfunction "17/GPIO5_17") (pintype "bidirectional"))
    )
    (net (code "67") (name "unconnected-(PCB1-18{slash}NC-Pad18)") (class "Default")
      (node (ref "PCB1") (pin "18") (pinfunction "18/NC_18") (pintype "bidirectional"))
    )
    (net (code "68") (name "unconnected-(PCB1-20{slash}NC-Pad20)") (class "Default")
      (node (ref "PCB1") (pin "20") (pinfunction "20/NC_20") (pintype "bidirectional"))
    )
    (net (code "69") (name "unconnected-(PCB1-21{slash}GPIO6-Pad21)") (class "Default")
      (node (ref "PCB1") (pin "21") (pinfunction "21/GPIO6_21") (pintype "bidirectional"))
    )
    (net (code "70") (name "unconnected-(PCB1-22{slash}NC-Pad22)") (class "Default")
      (node (ref "PCB1") (pin "22") (pinfunction "22/NC_22") (pintype "bidirectional"))
    )
    (net (code "71") (name "unconnected-(PCB1-23{slash}GPIO7-Pad23)") (class "Default")
      (node (ref "PCB1") (pin "23") (pinfunction "23/GPIO7_23") (pintype "bidirectional"))
    )
    (net (code "72") (name "unconnected-(PCB1-24{slash}NC-Pad24)") (class "Default")
      (node (ref "PCB1") (pin "24") (pinfunction "24/NC_24") (pintype "bidirectional"))
    )
    (net (code "73") (name "unconnected-(PCB1-27{slash}GPIO8-Pad27)") (class "Default")
      (node (ref "PCB1") (pin "27") (pinfunction "27/GPIO8_27") (pintype "bidirectional"))
    )
    (net (code "74") (name "unconnected-(PCB1-29{slash}GPIO9-Pad29)") (class "Default")
      (node (ref "PCB1") (pin "29") (pinfunction "29/GPIO9_29") (pintype "bidirectional"))
    )
    (net (code "75") (name "unconnected-(PCB1-33{slash}GPIO10-Pad33)") (class "Default")
      (node (ref "PCB1") (pin "33") (pinfunction "33/GPIO10_33") (pintype "bidirectional"))
    )
    (net (code "76") (name "unconnected-(PCB1-35{slash}GPIO11-Pad35)") (class "Default")
      (node (ref "PCB1") (pin "35") (pinfunction "35/GPIO11_35") (pintype "bidirectional"))
    )
    (net (code "77") (name "unconnected-(PCB1-45{slash}GPIO12-Pad45)") (class "Default")
      (node (ref "PCB1") (pin "45") (pinfunction "45/GPIO12_45") (pintype "bidirectional"))
    )
    (net (code "78") (name "unconnected-(PCB1-46{slash}GPIO32-Pad46)") (class "Default")
      (node (ref "PCB1") (pin "46") (pinfunction "46/GPIO32_46") (pintype "bidirectional"))
    )
    (net (code "79") (name "unconnected-(PCB1-47{slash}GPIO13-Pad47)") (class "Default")
      (node (ref "PCB1") (pin "47") (pinfunction "47/GPIO13_47") (pintype "bidirectional"))
    )
    (net (code "80") (name "unconnected-(PCB1-48{slash}GPIO33-Pad48)") (class "Default")
      (node (ref "PCB1") (pin "48") (pinfunction "48/GPIO33_48") (pintype "bidirectional"))
    )
    (net (code "81") (name "unconnected-(PCB1-52{slash}GPIO34-Pad52)") (class "Default")
      (node (ref "PCB1") (pin "52") (pinfunction "52/GPIO34_52") (pintype "bidirectional"))
    )
    (net (code "82") (name "unconnected-(PCB1-54{slash}GPIO35-Pad54)") (class "Default")
      (node (ref "PCB1") (pin "54") (pinfunction "54/GPIO35_54") (pintype "bidirectional"))
    )
    (net (code "83") (name "unconnected-(PCB1-58{slash}GPIO36-Pad58)") (class "Default")
      (node (ref "PCB1") (pin "58") (pinfunction "58/GPIO36_58") (pintype "bidirectional"))
    )
    (net (code "84") (name "unconnected-(PCB1-60{slash}GPIO37-Pad60)") (class "Default")
      (node (ref "PCB1") (pin "60") (pinfunction "60/GPIO37_60") (pintype "bidirectional"))
    )
    (net (code "85") (name "unconnected-(PCB1-63{slash}GPIO18-Pad63)") (class "Default")
      (node (ref "PCB1") (pin "63") (pinfunction "63/GPIO18_63") (pintype "bidirectional"))
    )
    (net (code "86") (name "unconnected-(PCB1-64{slash}GPIO38-Pad64)") (class "Default")
      (node (ref "PCB1") (pin "64") (pinfunction "64/GPIO38_64") (pintype "bidirectional"))
    )
    (net (code "87") (name "unconnected-(PCB1-65{slash}GPIO19-Pad65)") (class "Default")
      (node (ref "PCB1") (pin "65") (pinfunction "65/GPIO19_65") (pintype "bidirectional"))
    )
    (net (code "88") (name "unconnected-(PCB1-66{slash}GPIO39-Pad66)") (class "Default")
      (node (ref "PCB1") (pin "66") (pinfunction "66/GPIO39_66") (pintype "bidirectional"))
    )
    (net (code "89") (name "unconnected-(PCB1-69{slash}GPIO20-Pad69)") (class "Default")
      (node (ref "PCB1") (pin "69") (pinfunction "69/GPIO20_69") (pintype "bidirectional"))
    )
    (net (code "90") (name "unconnected-(PCB1-71{slash}GPIO21-Pad71)") (class "Default")
      (node (ref "PCB1") (pin "71") (pinfunction "71/GPIO21_71") (pintype "bidirectional"))
    )
    (net (code "91") (name "unconnected-(PCB1-75{slash}GPIO22-Pad75)") (class "Default")
      (node (ref "PCB1") (pin "75") (pinfunction "75/GPIO22_75") (pintype "bidirectional"))
    )
    (net (code "92") (name "unconnected-(PCB1-76{slash}GPIO42-Pad76)") (class "Default")
      (node (ref "PCB1") (pin "76") (pinfunction "76/GPIO42_76") (pintype "bidirectional"))
    )
    (net (code "93") (name "unconnected-(PCB1-77{slash}GPIO23-Pad77)") (class "Default")
      (node (ref "PCB1") (pin "77") (pinfunction "77/GPIO23_77") (pintype "bidirectional"))
    )
    (net (code "94") (name "unconnected-(PCB1-78{slash}GPIO43-Pad78)") (class "Default")
      (node (ref "PCB1") (pin "78") (pinfunction "78/GPIO43_78") (pintype "bidirectional"))
    )
    (net (code "95") (name "unconnected-(PCB1-81{slash}GPIO24-Pad81)") (class "Default")
      (node (ref "PCB1") (pin "81") (pinfunction "81/GPIO24_81") (pintype "bidirectional"))
    )
    (net (code "96") (name "unconnected-(PCB1-83{slash}GPIO25-Pad83)") (class "Default")
      (node (ref "PCB1") (pin "83") (pinfunction "83/GPIO25_83") (pintype "bidirectional"))
    )
    (net (code "97") (name "unconnected-(PCB1-87{slash}GPIO26-Pad87)") (class "Default")
      (node (ref "PCB1") (pin "87") (pinfunction "87/GPIO26_87") (pintype "bidirectional"))
    )
    (net (code "98") (name "unconnected-(PCB1-88{slash}GPIO46_1V8-Pad88)") (class "Default")
      (node (ref "PCB1") (pin "88") (pinfunction "88/GPIO46_1V8_88") (pintype "bidirectional"))
    )
    (net (code "99") (name "unconnected-(PCB1-89{slash}GPIO27-Pad89)") (class "Default")
      (node (ref "PCB1") (pin "89") (pinfunction "89/GPIO27_89") (pintype "bidirectional"))
    )
    (net (code "100") (name "unconnected-(PCB1-93{slash}DSI0_DN1*-Pad93)") (class "Default")
      (node (ref "PCB1") (pin "93") (pinfunction "93/DSI0_DN1*_93") (pintype "bidirectional"))
    )
    (net (code "101") (name "unconnected-(PCB1-94{slash}DSI1_DP0*-Pad94)") (class "Default")
      (node (ref "PCB1") (pin "94") (pinfunction "94/DSI1_DP0*_94") (pintype "bidirectional"))
    )
    (net (code "102") (name "unconnected-(PCB1-95{slash}DSI0_DP1*-Pad95)") (class "Default")
      (node (ref "PCB1") (pin "95") (pinfunction "95/DSI0_DP1*_95") (pintype "bidirectional"))
    )
    (net (code "103") (name "unconnected-(PCB1-96{slash}DSI1_DN0*-Pad96)") (class "Default")
      (node (ref "PCB1") (pin "96") (pinfunction "96/DSI1_DN0*_96") (pintype "bidirectional"))
    )
    (net (code "104") (name "unconnected-(PCB1-99{slash}DSI0_DN0*-Pad99)") (class "Default")
      (node (ref "PCB1") (pin "99") (pinfunction "99/DSI0_DN0*_99") (pintype "bidirectional"))
    )
    (net (code "105") (name "unconnected-(PCB1-100{slash}DSI1CP*-Pad100)") (class "Default")
      (node (ref "PCB1") (pin "100") (pinfunction "100/DSI1CP*_100") (pintype "bidirectional"))
    )
    (net (code "106") (name "unconnected-(PCB1-101{slash}DSI0_DP0*-Pad101)") (class "Default")
      (node (ref "PCB1") (pin "101") (pinfunction "101/DSI0_DP0*_101") (pintype "bidirectional"))
    )
    (net (code "107") (name "unconnected-(PCB1-102{slash}DSI1CN*-Pad102)") (class "Default")
      (node (ref "PCB1") (pin "102") (pinfunction "102/DSI1CN*_102") (pintype "bidirectional"))
    )
    (net (code "108") (name "unconnected-(PCB1-105{slash}DSI0_CN*-Pad105)") (class "Default")
      (node (ref "PCB1") (pin "105") (pinfunction "105/DSI0_CN*_105") (pintype "bidirectional"))
    )
    (net (code "109") (name "unconnected-(PCB1-106{slash}DSI1_DP3*-Pad106)") (class "Default")
      (node (ref "PCB1") (pin "106") (pinfunction "106/DSI1_DP3*_106") (pintype "bidirectional"))
    )
    (net (code "110") (name "unconnected-(PCB1-107{slash}DSI0_CP*-Pad107)") (class "Default")
      (node (ref "PCB1") (pin "107") (pinfunction "107/DSI0_CP*_107") (pintype "bidirectional"))
    )
    (net (code "111") (name "unconnected-(PCB1-108{slash}DSI1_DN3*-Pad108)") (class "Default")
      (node (ref "PCB1") (pin "108") (pinfunction "108/DSI1_DN3*_108") (pintype "bidirectional"))
    )
    (net (code "112") (name "unconnected-(PCB1-111{slash}HDMI_CK_N*-Pad111)") (class "Default")
      (node (ref "PCB1") (pin "111") (pinfunction "111/HDMI_CK_N*_111") (pintype "bidirectional"))
    )
    (net (code "113") (name "unconnected-(PCB1-112{slash}DSI1_DP2*-Pad112)") (class "Default")
      (node (ref "PCB1") (pin "112") (pinfunction "112/DSI1_DP2*_112") (pintype "bidirectional"))
    )
    (net (code "114") (name "unconnected-(PCB1-113{slash}HDMI_CK_P*-Pad113)") (class "Default")
      (node (ref "PCB1") (pin "113") (pinfunction "113/HDMI_CK_P*_113") (pintype "bidirectional"))
    )
    (net (code "115") (name "unconnected-(PCB1-114{slash}DSI1_DN2*-Pad114)") (class "Default")
      (node (ref "PCB1") (pin "114") (pinfunction "114/DSI1_DN2*_114") (pintype "bidirectional"))
    )
    (net (code "116") (name "unconnected-(PCB1-116{slash}GND-Pad116)") (class "Default")
      (node (ref "PCB1") (pin "116") (pinfunction "116/GND_116") (pintype "bidirectional"))
    )
    (net (code "117") (name "unconnected-(PCB1-117{slash}HDMI_D0_N*-Pad117)") (class "Default")
      (node (ref "PCB1") (pin "117") (pinfunction "117/HDMI_D0_N*_117") (pintype "bidirectional"))
    )
    (net (code "118") (name "unconnected-(PCB1-118{slash}DSI1_DP1*-Pad118)") (class "Default")
      (node (ref "PCB1") (pin "118") (pinfunction "118/DSI1_DP1*_118") (pintype "bidirectional"))
    )
    (net (code "119") (name "unconnected-(PCB1-119{slash}HDMI_D0_P*-Pad119)") (class "Default")
      (node (ref "PCB1") (pin "119") (pinfunction "119/HDMI_D0_P*_119") (pintype "bidirectional"))
    )
    (net (code "120") (name "unconnected-(PCB1-120{slash}DSI1_DN1*-Pad120)") (class "Default")
      (node (ref "PCB1") (pin "120") (pinfunction "120/DSI1_DN1*_120") (pintype "bidirectional"))
    )
    (net (code "121") (name "unconnected-(PCB1-123{slash}HDMI_D1_N*-Pad123)") (class "Default")
      (node (ref "PCB1") (pin "123") (pinfunction "123/HDMI_D1_N*_123") (pintype "bidirectional"))
    )
    (net (code "122") (name "unconnected-(PCB1-124{slash}NC-Pad124)") (class "Default")
      (node (ref "PCB1") (pin "124") (pinfunction "124/NC_124") (pintype "bidirectional"))
    )
    (net (code "123") (name "unconnected-(PCB1-125{slash}HDMI_D1_P*-Pad125)") (class "Default")
      (node (ref "PCB1") (pin "125") (pinfunction "125/HDMI_D1_P*_125") (pintype "bidirectional"))
    )
    (net (code "124") (name "unconnected-(PCB1-126{slash}NC-Pad126)") (class "Default")
      (node (ref "PCB1") (pin "126") (pinfunction "126/NC_126") (pintype "bidirectional"))
    )
    (net (code "125") (name "unconnected-(PCB1-128{slash}NC-Pad128)") (class "Default")
      (node (ref "PCB1") (pin "128") (pinfunction "128/NC_128") (pintype "bidirectional"))
    )
    (net (code "126") (name "unconnected-(PCB1-129{slash}HDMI_D2_N*-Pad129)") (class "Default")
      (node (ref "PCB1") (pin "129") (pinfunction "129/HDMI_D2_N*_129") (pintype "bidirectional"))
    )
    (net (code "127") (name "unconnected-(PCB1-130{slash}NC-Pad130)") (class "Default")
      (node (ref "PCB1") (pin "130") (pinfunction "130/NC_130") (pintype "bidirectional"))
    )
    (net (code "128") (name "unconnected-(PCB1-131{slash}HDMI_D2_P*-Pad131)") (class "Default")
      (node (ref "PCB1") (pin "131") (pinfunction "131/HDMI_D2_P*_131") (pintype "bidirectional"))
    )
    (net (code "129") (name "unconnected-(PCB1-132{slash}NC-Pad132)") (class "Default")
      (node (ref "PCB1") (pin "132") (pinfunction "132/NC_132") (pintype "bidirectional"))
    )
    (net (code "130") (name "unconnected-(PCB1-135{slash}CAM1_DP3*-Pad135)") (class "Default")
      (node (ref "PCB1") (pin "135") (pinfunction "135/CAM1_DP3*_135") (pintype "bidirectional"))
    )
    (net (code "131") (name "unconnected-(PCB1-137{slash}CAM1_DN3*-Pad137)") (class "Default")
      (node (ref "PCB1") (pin "137") (pinfunction "137/CAM1_DN3*_137") (pintype "bidirectional"))
    )
    (net (code "132") (name "unconnected-(PCB1-141{slash}CAM1_DP2*-Pad141)") (class "Default")
      (node (ref "PCB1") (pin "141") (pinfunction "141/CAM1_DP2*_141") (pintype "bidirectional"))
    )
    (net (code "133") (name "unconnected-(PCB1-143{slash}CAM1_DN2*-Pad143)") (class "Default")
      (node (ref "PCB1") (pin "143") (pinfunction "143/CAM1_DN2*_143") (pintype "bidirectional"))
    )
    (net (code "134") (name "unconnected-(PCB1-154{slash}NC-Pad154)") (class "Default")
      (node (ref "PCB1") (pin "154") (pinfunction "154/NC_154") (pintype "bidirectional"))
    )
    (net (code "135") (name "unconnected-(PCB1-156{slash}NC-Pad156)") (class "Default")
      (node (ref "PCB1") (pin "156") (pinfunction "156/NC_156") (pintype "bidirectional"))
    )
    (net (code "136") (name "unconnected-(PCB1-158{slash}NC-Pad158)") (class "Default")
      (node (ref "PCB1") (pin "158") (pinfunction "158/NC_158") (pintype "bidirectional"))
    )
    (net (code "137") (name "unconnected-(PCB1-160{slash}NC-Pad160)") (class "Default")
      (node (ref "PCB1") (pin "160") (pinfunction "160/NC_160") (pintype "bidirectional"))
    )
    (net (code "138") (name "unconnected-(PCB1-162{slash}NC-Pad162)") (class "Default")
      (node (ref "PCB1") (pin "162") (pinfunction "162/NC_162") (pintype "bidirectional"))
    )
    (net (code "139") (name "unconnected-(PCB1-166{slash}TVDAC-Pad166)") (class "Default")
      (node (ref "PCB1") (pin "166") (pinfunction "166/TVDAC_166") (pintype "bidirectional"))
    )
    (net (code "140") (name "unconnected-(PCB1-168{slash}USB_OTGID-Pad168)") (class "Default")
      (node (ref "PCB1") (pin "168") (pinfunction "168/USB_OTGID_168") (pintype "bidirectional"))
    )
    (net (code "141") (name "unconnected-(PCB1-171{slash}HDMI_CEC-Pad171)") (class "Default")
      (node (ref "PCB1") (pin "171") (pinfunction "171/HDMI_CEC_171") (pintype "bidirectional"))
    )
    (net (code "142") (name "unconnected-(PCB1-172{slash}VC_TRST_N-Pad172)") (class "Default")
      (node (ref "PCB1") (pin "172") (pinfunction "172/VC_TRST_N_172") (pintype "bidirectional"))
    )
    (net (code "143") (name "unconnected-(PCB1-173{slash}HDMI_SDA-Pad173)") (class "Default")
      (node (ref "PCB1") (pin "173") (pinfunction "173/HDMI_SDA_173") (pintype "bidirectional"))
    )
    (net (code "144") (name "unconnected-(PCB1-174{slash}VC_TDI-Pad174)") (class "Default")
      (node (ref "PCB1") (pin "174") (pinfunction "174/VC_TDI_174") (pintype "bidirectional"))
    )
    (net (code "145") (name "unconnected-(PCB1-175{slash}HDMI_SCL-Pad175)") (class "Default")
      (node (ref "PCB1") (pin "175") (pinfunction "175/HDMI_SCL_175") (pintype "bidirectional"))
    )
    (net (code "146") (name "unconnected-(PCB1-176{slash}VC_TMS-Pad176)") (class "Default")
      (node (ref "PCB1") (pin "176") (pinfunction "176/VC_TMS_176") (pintype "bidirectional"))
    )
    (net (code "147") (name "unconnected-(PCB1-177{slash}RUN-Pad177)") (class "Default")
      (node (ref "PCB1") (pin "177") (pinfunction "177/RUN_177") (pintype "bidirectional"))
    )
    (net (code "148") (name "unconnected-(PCB1-178{slash}VC_TDO-Pad178)") (class "Default")
      (node (ref "PCB1") (pin "178") (pinfunction "178/VC_TDO_178") (pintype "bidirectional"))
    )
    (net (code "149") (name "unconnected-(PCB1-179{slash}VDD_CORE-Pad179)") (class "Default")
      (node (ref "PCB1") (pin "179") (pinfunction "179/VDD_CORE_179") (pintype "bidirectional"))
    )
    (net (code "150") (name "unconnected-(PCB1-180{slash}VC_TCK-Pad180)") (class "Default")
      (node (ref "PCB1") (pin "180") (pinfunction "180/VC_TCK_180") (pintype "bidirectional"))
    )
    (net (code "151") (name "unconnected-(U4-SIG0-Pad9)") (class "Default")
      (node (ref "U4") (pin "9") (pinfunction "SIG0_9") (pintype "bidirectional"))
    )
    (net (code "152") (name "unconnected-(U4-SIG1-Pad10)") (class "Default")
      (node (ref "U4") (pin "10") (pinfunction "SIG1_10") (pintype "bidirectional"))
    )
    (net (code "153") (name "unconnected-(U4-SIG2-Pad11)") (class "Default")
      (node (ref "U4") (pin "11") (pinfunction "SIG2_11") (pintype "bidirectional"))
    )
    (net (code "154") (name "unconnected-(U5-NC1-Pad5)") (class "Default")
      (node (ref "U5") (pin "5") (pinfunction "NC1_5") (pintype "bidirectional"))
    )
    (net (code "155") (name "unconnected-(U5-NC2-Pad11)") (class "Default")
      (node (ref "U5") (pin "11") (pinfunction "NC2_11") (pintype "bidirectional"))
    )
  )
)
